# Plugs.net
KiCad netlist of a schematic drawn in Altium Designer
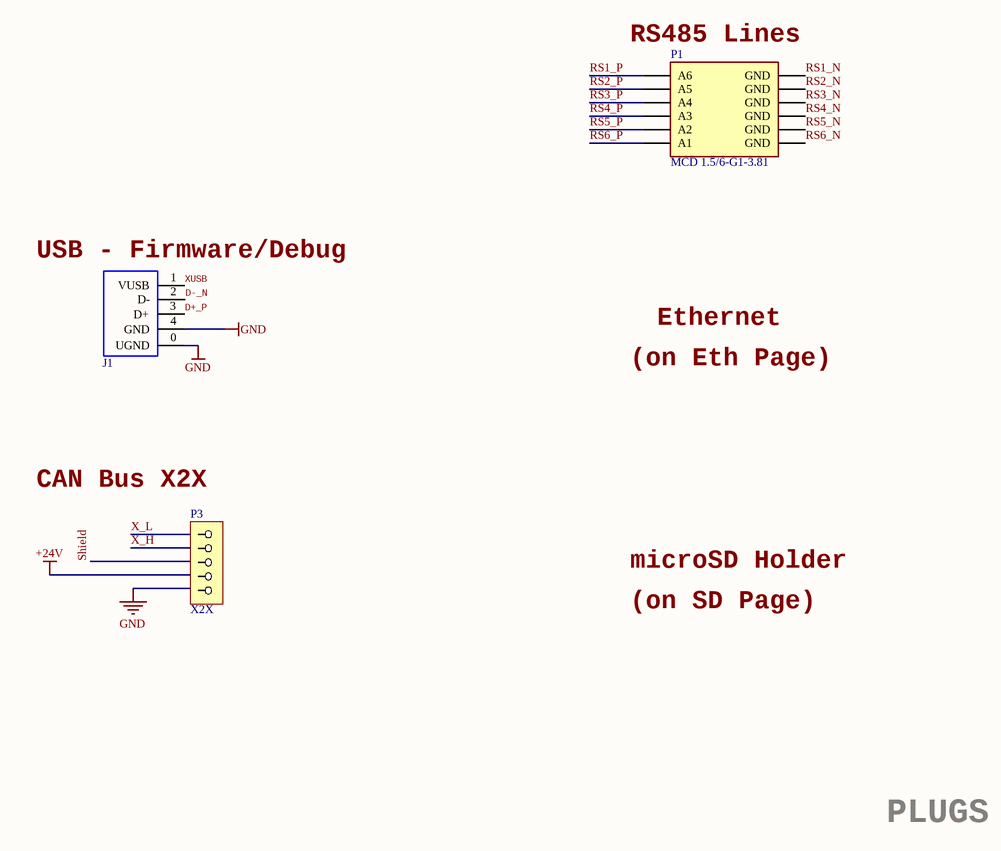
[diagram p0: Plugs.SchDoc]

(export (version "E")
  (design (tool "Eeschema 10.0.6"))
  (components
    (comp (ref "J1") (value "USBB-1J") (footprint "USB B") (libsource (lib "kontr") (part "USBB-1J")))
    (comp (ref "P1")
      (value "MCD 1.5/6-G1-3.81")
      (footprint "mcd 1,5/6-G1-3.81")
      (description "Header, 6-Pin, Dual row")
      (fields (field (name "PUBLISHER") "Altium Limited"))
      (libsource (lib "kontr") (part "Header 6X2"))
    )
    (comp (ref "P3")
      (value "X2X")
      (footprint "PhClass5")
      (description "EMSTBA 2.5/5-G-5.08")
      (libsource (lib "kontr") (part "EMSTBA 2.5/5-G-5.08"))
    )
  )
  (nets
    (net (code "1") (name "+24V") (class "Default")
      (node (ref "P3") (pin "4") (pinfunction "2_4") (pintype "passive"))
    )
    (net (code "2") (name "/D+_P") (class "Default")
      (node (ref "J1") (pin "3") (pinfunction "D+_3") (pintype "passive"))
    )
    (net (code "3") (name "/D-_N") (class "Default")
      (node (ref "J1") (pin "2") (pinfunction "D-_2") (pintype "passive"))
    )
    (net (code "4") (name "/RS1_N") (class "Default")
      (node (ref "P1") (pin "2") (pinfunction "GND_2") (pintype "passive"))
    )
    (net (code "5") (name "/RS1_P") (class "Default")
      (node (ref "P1") (pin "1") (pinfunction "A6_1") (pintype "passive"))
    )
    (net (code "6") (name "/RS2_N") (class "Default")
      (node (ref "P1") (pin "4") (pinfunction "GND_4") (pintype "passive"))
    )
    (net (code "7") (name "/RS2_P") (class "Default")
      (node (ref "P1") (pin "3") (pinfunction "A5_3") (pintype "passive"))
    )
    (net (code "8") (name "/RS3_N") (class "Default")
      (node (ref "P1") (pin "6") (pinfunction "GND_6") (pintype "passive"))
    )
    (net (code "9") (name "/RS3_P") (class "Default")
      (node (ref "P1") (pin "5") (pinfunction "A4_5") (pintype "passive"))
    )
    (net (code "10") (name "/RS4_N") (class "Default")
      (node (ref "P1") (pin "8") (pinfunction "GND_8") (pintype "passive"))
    )
    (net (code "11") (name "/RS4_P") (class "Default")
      (node (ref "P1") (pin "7") (pinfunction "A3_7") (pintype "passive"))
    )
    (net (code "12") (name "/RS5_N") (class "Default")
      (node (ref "P1") (pin "10") (pinfunction "GND_10") (pintype "passive"))
    )
    (net (code "13") (name "/RS5_P") (class "Default")
      (node (ref "P1") (pin "9") (pinfunction "A2_9") (pintype "passive"))
    )
    (net (code "14") (name "/RS6_N") (class "Default")
      (node (ref "P1") (pin "12") (pinfunction "GND_12") (pintype "passive"))
    )
    (net (code "15") (name "/RS6_P") (class "Default")
      (node (ref "P1") (pin "11") (pinfunction "A1_11") (pintype "passive"))
    )
    (net (code "16") (name "/Shield") (class "Default")
      (node (ref "P3") (pin "3") (pinfunction "3_3") (pintype "passive"))
    )
    (net (code "17") (name "/XUSB") (class "Default")
      (node (ref "J1") (pin "1") (pinfunction "VUSB_1") (pintype "passive"))
    )
    (net (code "18") (name "/X_H") (class "Default")
      (node (ref "P3") (pin "2") (pinfunction "2_2") (pintype "passive"))
    )
    (net (code "19") (name "/X_L") (class "Default")
      (node (ref "P3") (pin "1") (pinfunction "1_1") (pintype "passive"))
    )
    (net (code "20") (name "GND") (class "Default")
      (node (ref "J1") (pin "0") (pinfunction "UGND_0") (pintype "passive"))
      (node (ref "J1") (pin "4") (pinfunction "GND_4") (pintype "passive"))
      (node (ref "P3") (pin "5") (pinfunction "3_5") (pintype "passive"))
    )
  )
)
